# AVRI2CIO.net
KiCad netlist of a schematic drawn in EAGLE
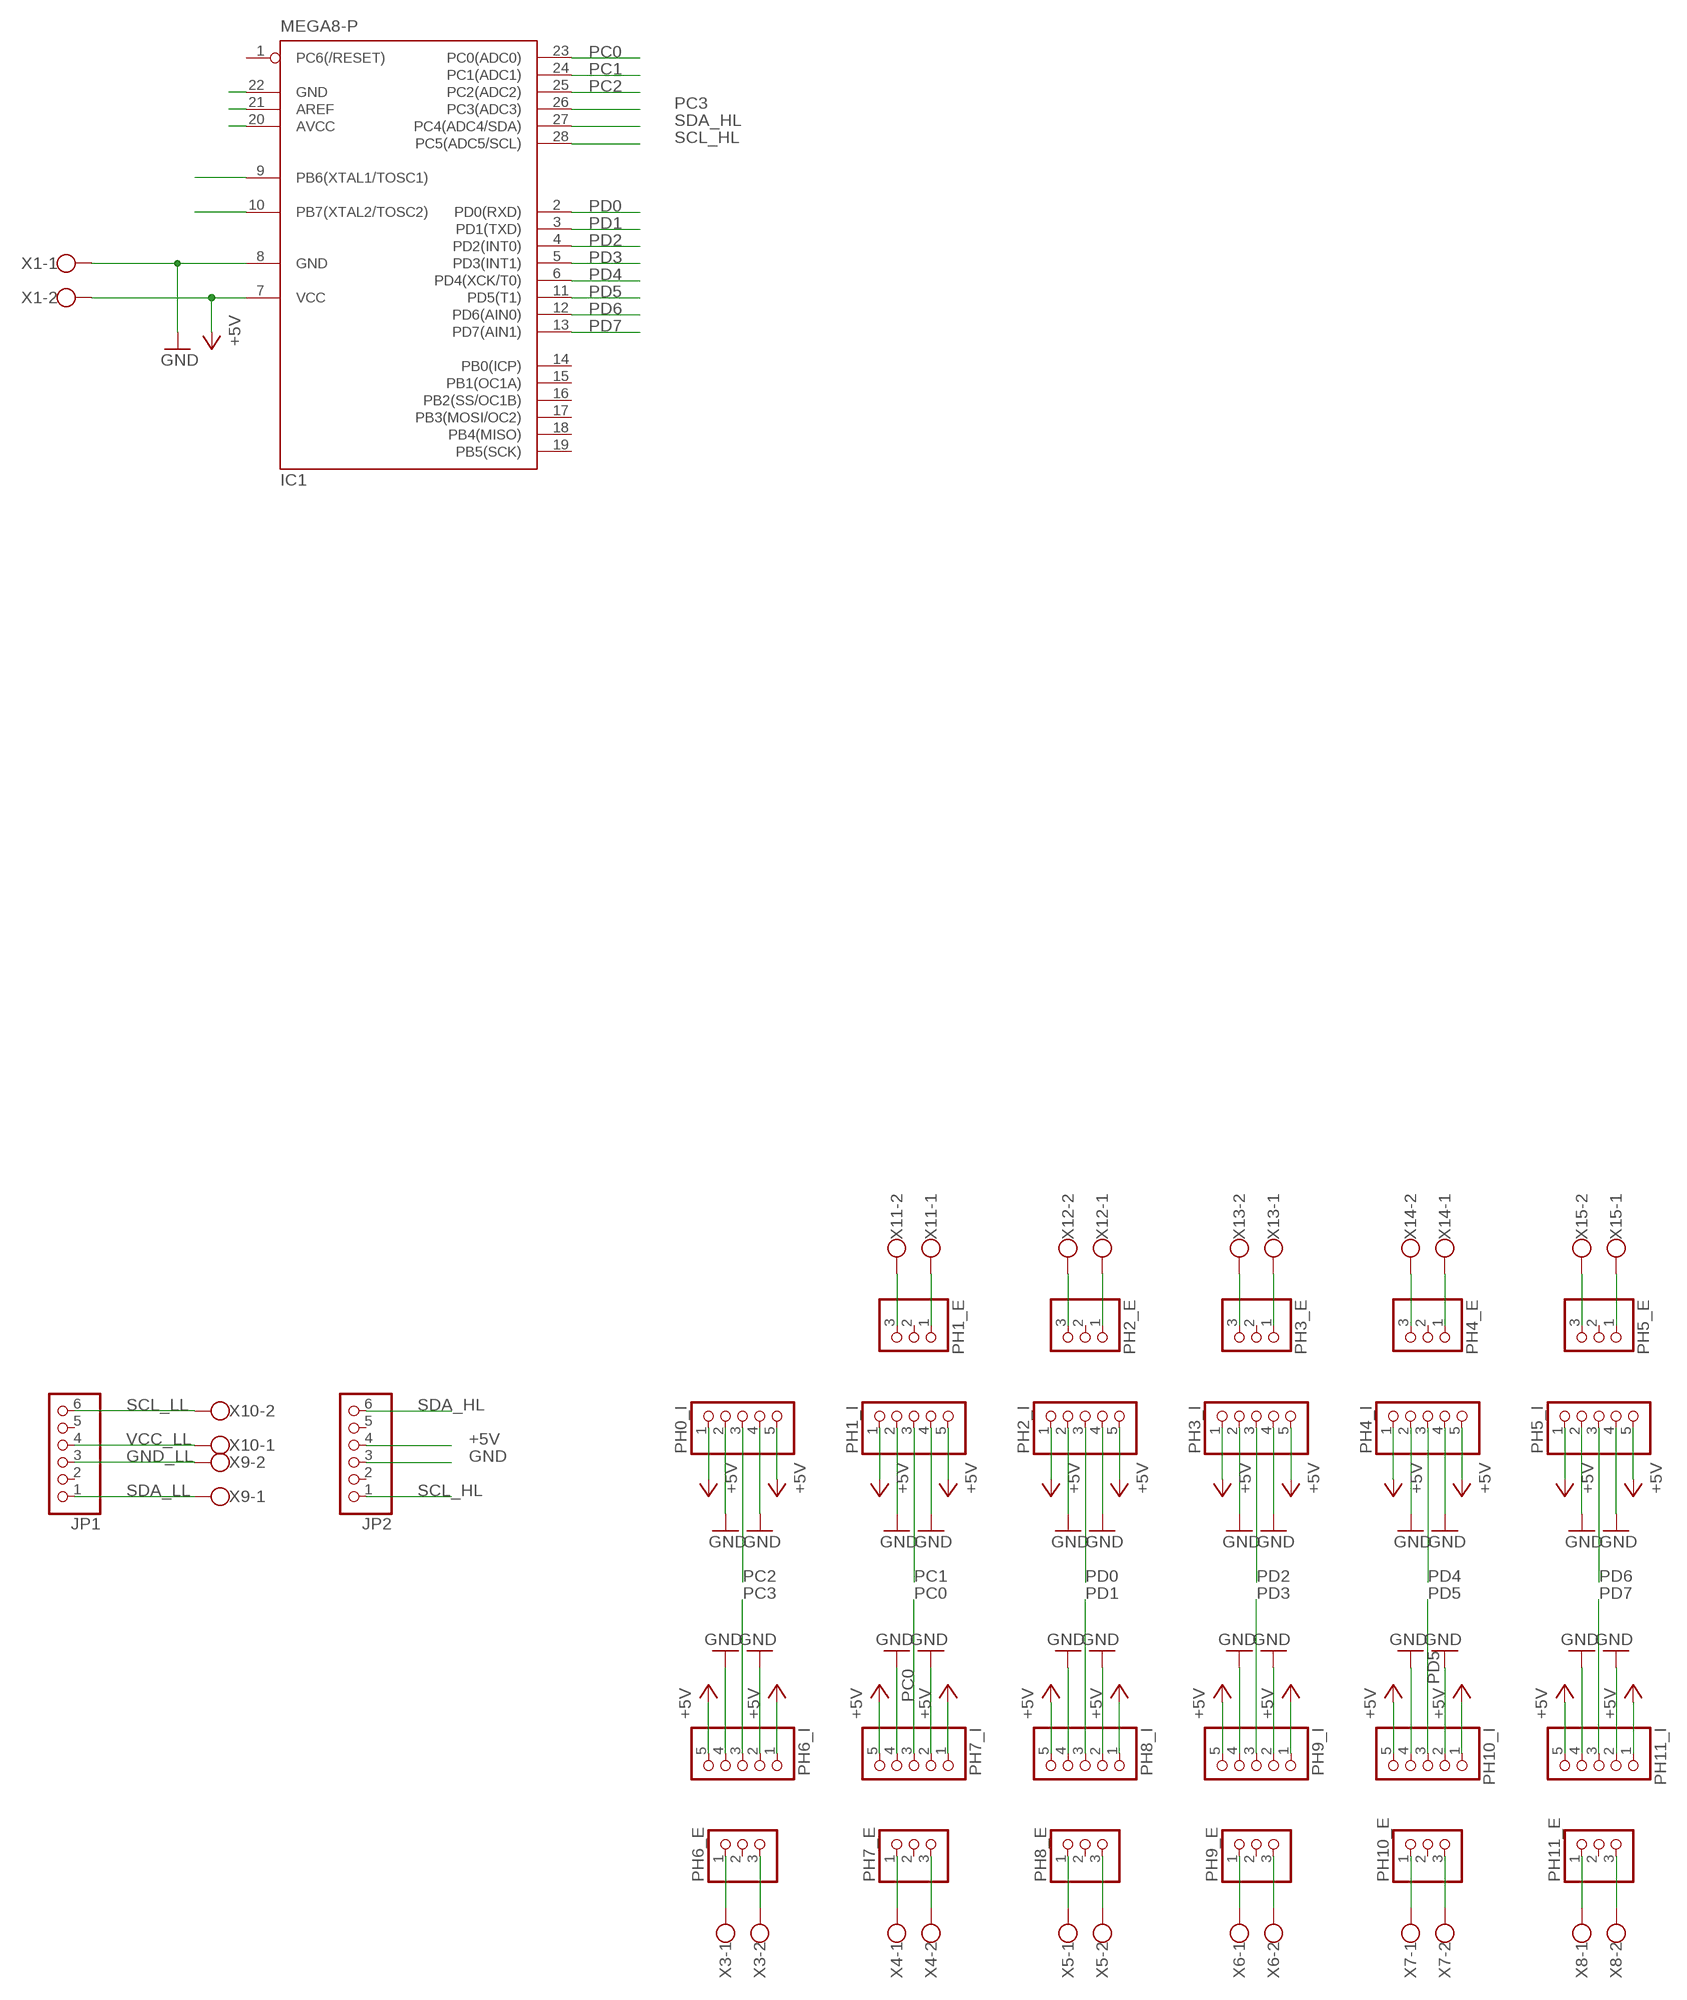
[diagram p0: schematic, sheet 1]

(export (version "E")
  (design (tool "Eeschema 10.0.6"))
  (components
    (comp (ref "IC1")
      (value "MEGA8-P")
      (footprint "eagle-import:DIL28-3")
      (libsource (lib "eagle-import") (part "MEGA8-P"))
    )
    (comp (ref "JP1")
      (value "PINHD-1X6")
      (footprint "eagle-import:1X06")
      (libsource (lib "eagle-import") (part "PINHD-1X6"))
    )
    (comp (ref "JP2")
      (value "PINHD-1X6")
      (footprint "eagle-import:1X06")
      (libsource (lib "eagle-import") (part "PINHD-1X6"))
    )
    (comp (ref "PH0_I")
      (value "PINHD-1X5")
      (footprint "eagle-import:1X05")
      (libsource (lib "eagle-import") (part "PINHD-1X5"))
    )
    (comp (ref "PH1_E")
      (value "PINHD-1X3")
      (footprint "eagle-import:1X03")
      (libsource (lib "eagle-import") (part "PINHD-1X3"))
    )
    (comp (ref "PH1_I")
      (value "PINHD-1X5")
      (footprint "eagle-import:1X05")
      (libsource (lib "eagle-import") (part "PINHD-1X5"))
    )
    (comp (ref "PH2_E")
      (value "PINHD-1X3")
      (footprint "eagle-import:1X03")
      (libsource (lib "eagle-import") (part "PINHD-1X3"))
    )
    (comp (ref "PH2_I")
      (value "PINHD-1X5")
      (footprint "eagle-import:1X05")
      (libsource (lib "eagle-import") (part "PINHD-1X5"))
    )
    (comp (ref "PH3_E")
      (value "PINHD-1X3")
      (footprint "eagle-import:1X03")
      (libsource (lib "eagle-import") (part "PINHD-1X3"))
    )
    (comp (ref "PH3_I")
      (value "PINHD-1X5")
      (footprint "eagle-import:1X05")
      (libsource (lib "eagle-import") (part "PINHD-1X5"))
    )
    (comp (ref "PH4_E")
      (value "PINHD-1X3")
      (footprint "eagle-import:1X03")
      (libsource (lib "eagle-import") (part "PINHD-1X3"))
    )
    (comp (ref "PH4_I")
      (value "PINHD-1X5")
      (footprint "eagle-import:1X05")
      (libsource (lib "eagle-import") (part "PINHD-1X5"))
    )
    (comp (ref "PH5_E")
      (value "PINHD-1X3")
      (footprint "eagle-import:1X03")
      (libsource (lib "eagle-import") (part "PINHD-1X3"))
    )
    (comp (ref "PH5_I")
      (value "PINHD-1X5")
      (footprint "eagle-import:1X05")
      (libsource (lib "eagle-import") (part "PINHD-1X5"))
    )
    (comp (ref "PH6_E")
      (value "PINHD-1X3")
      (footprint "eagle-import:1X03")
      (libsource (lib "eagle-import") (part "PINHD-1X3"))
    )
    (comp (ref "PH6_I")
      (value "PINHD-1X5")
      (footprint "eagle-import:1X05")
      (libsource (lib "eagle-import") (part "PINHD-1X5"))
    )
    (comp (ref "PH7_E")
      (value "PINHD-1X3")
      (footprint "eagle-import:1X03")
      (libsource (lib "eagle-import") (part "PINHD-1X3"))
    )
    (comp (ref "PH7_I")
      (value "PINHD-1X5")
      (footprint "eagle-import:1X05")
      (libsource (lib "eagle-import") (part "PINHD-1X5"))
    )
    (comp (ref "PH8_E")
      (value "PINHD-1X3")
      (footprint "eagle-import:1X03")
      (libsource (lib "eagle-import") (part "PINHD-1X3"))
    )
    (comp (ref "PH8_I")
      (value "PINHD-1X5")
      (footprint "eagle-import:1X05")
      (libsource (lib "eagle-import") (part "PINHD-1X5"))
    )
    (comp (ref "PH9_E")
      (value "PINHD-1X3")
      (footprint "eagle-import:1X03")
      (libsource (lib "eagle-import") (part "PINHD-1X3"))
    )
    (comp (ref "PH9_I")
      (value "PINHD-1X5")
      (footprint "eagle-import:1X05")
      (libsource (lib "eagle-import") (part "PINHD-1X5"))
    )
    (comp (ref "PH10_E")
      (value "PINHD-1X3")
      (footprint "eagle-import:1X03")
      (libsource (lib "eagle-import") (part "PINHD-1X3"))
    )
    (comp (ref "PH10_I")
      (value "PINHD-1X5")
      (footprint "eagle-import:1X05")
      (libsource (lib "eagle-import") (part "PINHD-1X5"))
    )
    (comp (ref "PH11_E")
      (value "PINHD-1X3")
      (footprint "eagle-import:1X03")
      (libsource (lib "eagle-import") (part "PINHD-1X3"))
    )
    (comp (ref "PH11_I")
      (value "PINHD-1X5")
      (footprint "eagle-import:1X05")
      (libsource (lib "eagle-import") (part "PINHD-1X5"))
    )
    (comp (ref "X1")
      (value "W237-102")
      (footprint "eagle-import:W237-102")
      (fields (field (name "MPN") "237-102"))
      (libsource (lib "eagle-import") (part "W237-102"))
    )
    (comp (ref "X3")
      (value "W237-102")
      (footprint "eagle-import:W237-102")
      (fields (field (name "MPN") "237-102"))
      (libsource (lib "eagle-import") (part "W237-102"))
    )
    (comp (ref "X4")
      (value "W237-102")
      (footprint "eagle-import:W237-102")
      (fields (field (name "MPN") "237-102"))
      (libsource (lib "eagle-import") (part "W237-102"))
    )
    (comp (ref "X5")
      (value "W237-102")
      (footprint "eagle-import:W237-102")
      (fields (field (name "MPN") "237-102"))
      (libsource (lib "eagle-import") (part "W237-102"))
    )
    (comp (ref "X6")
      (value "W237-102")
      (footprint "eagle-import:W237-102")
      (fields (field (name "MPN") "237-102"))
      (libsource (lib "eagle-import") (part "W237-102"))
    )
    (comp (ref "X7")
      (value "W237-102")
      (footprint "eagle-import:W237-102")
      (fields (field (name "MPN") "237-102"))
      (libsource (lib "eagle-import") (part "W237-102"))
    )
    (comp (ref "X8")
      (value "W237-102")
      (footprint "eagle-import:W237-102")
      (fields (field (name "MPN") "237-102"))
      (libsource (lib "eagle-import") (part "W237-102"))
    )
    (comp (ref "X9")
      (value "W237-102")
      (footprint "eagle-import:W237-102")
      (fields (field (name "MPN") "237-102"))
      (libsource (lib "eagle-import") (part "W237-102"))
    )
    (comp (ref "X10")
      (value "W237-102")
      (footprint "eagle-import:W237-102")
      (fields (field (name "MPN") "237-102"))
      (libsource (lib "eagle-import") (part "W237-102"))
    )
    (comp (ref "X11")
      (value "W237-102")
      (footprint "eagle-import:W237-102")
      (fields (field (name "MPN") "237-102"))
      (libsource (lib "eagle-import") (part "W237-102"))
    )
    (comp (ref "X12")
      (value "W237-102")
      (footprint "eagle-import:W237-102")
      (fields (field (name "MPN") "237-102"))
      (libsource (lib "eagle-import") (part "W237-102"))
    )
    (comp (ref "X13")
      (value "W237-102")
      (footprint "eagle-import:W237-102")
      (fields (field (name "MPN") "237-102"))
      (libsource (lib "eagle-import") (part "W237-102"))
    )
    (comp (ref "X14")
      (value "W237-102")
      (footprint "eagle-import:W237-102")
      (fields (field (name "MPN") "237-102"))
      (libsource (lib "eagle-import") (part "W237-102"))
    )
    (comp (ref "X15")
      (value "W237-102")
      (footprint "eagle-import:W237-102")
      (fields (field (name "MPN") "237-102"))
      (libsource (lib "eagle-import") (part "W237-102"))
    )
  )
  (nets
    (net (code "1") (name "+5V") (class "Default")
      (node (ref "IC1") (pin "7") (pinfunction "VCC_7") (pintype "power_in"))
      (node (ref "JP2") (pin "4") (pinfunction "4_4") (pintype "passive"))
      (node (ref "PH0_I") (pin "1") (pinfunction "1_1") (pintype "passive"))
      (node (ref "PH0_I") (pin "5") (pinfunction "5_5") (pintype "passive"))
      (node (ref "PH10_I") (pin "1") (pinfunction "1_1") (pintype "passive"))
      (node (ref "PH10_I") (pin "5") (pinfunction "5_5") (pintype "passive"))
      (node (ref "PH11_I") (pin "1") (pinfunction "1_1") (pintype "passive"))
      (node (ref "PH11_I") (pin "5") (pinfunction "5_5") (pintype "passive"))
      (node (ref "PH1_I") (pin "1") (pinfunction "1_1") (pintype "passive"))
      (node (ref "PH1_I") (pin "5") (pinfunction "5_5") (pintype "passive"))
      (node (ref "PH2_I") (pin "1") (pinfunction "1_1") (pintype "passive"))
      (node (ref "PH2_I") (pin "5") (pinfunction "5_5") (pintype "passive"))
      (node (ref "PH3_I") (pin "1") (pinfunction "1_1") (pintype "passive"))
      (node (ref "PH3_I") (pin "5") (pinfunction "5_5") (pintype "passive"))
      (node (ref "PH4_I") (pin "1") (pinfunction "1_1") (pintype "passive"))
      (node (ref "PH4_I") (pin "5") (pinfunction "5_5") (pintype "passive"))
      (node (ref "PH5_I") (pin "1") (pinfunction "1_1") (pintype "passive"))
      (node (ref "PH5_I") (pin "5") (pinfunction "5_5") (pintype "passive"))
      (node (ref "PH6_I") (pin "1") (pinfunction "1_1") (pintype "passive"))
      (node (ref "PH6_I") (pin "5") (pinfunction "5_5") (pintype "passive"))
      (node (ref "PH7_I") (pin "1") (pinfunction "1_1") (pintype "passive"))
      (node (ref "PH7_I") (pin "5") (pinfunction "5_5") (pintype "passive"))
      (node (ref "PH8_I") (pin "1") (pinfunction "1_1") (pintype "passive"))
      (node (ref "PH8_I") (pin "5") (pinfunction "5_5") (pintype "passive"))
      (node (ref "PH9_I") (pin "1") (pinfunction "1_1") (pintype "passive"))
      (node (ref "PH9_I") (pin "5") (pinfunction "5_5") (pintype "passive"))
      (node (ref "X1") (pin "2") (pinfunction "KL_2") (pintype "passive"))
    )
    (net (code "2") (name "/GND_LL") (class "Default")
      (node (ref "JP1") (pin "3") (pinfunction "3_3") (pintype "passive"))
      (node (ref "X9") (pin "2") (pinfunction "KL_2") (pintype "passive"))
    )
    (net (code "3") (name "/PC0") (class "Default")
      (node (ref "IC1") (pin "23") (pinfunction "PC0(ADC0)_23") (pintype "bidirectional"))
      (node (ref "PH7_I") (pin "3") (pinfunction "3_3") (pintype "passive"))
    )
    (net (code "4") (name "/PC1") (class "Default")
      (node (ref "IC1") (pin "24") (pinfunction "PC1(ADC1)_24") (pintype "bidirectional"))
      (node (ref "PH1_I") (pin "3") (pinfunction "3_3") (pintype "passive"))
    )
    (net (code "5") (name "/PC2") (class "Default")
      (node (ref "IC1") (pin "25") (pinfunction "PC2(ADC2)_25") (pintype "bidirectional"))
      (node (ref "PH0_I") (pin "3") (pinfunction "3_3") (pintype "passive"))
    )
    (net (code "6") (name "/PC3") (class "Default")
      (node (ref "IC1") (pin "26") (pinfunction "PC3(ADC3)_26") (pintype "bidirectional"))
      (node (ref "PH6_I") (pin "3") (pinfunction "3_3") (pintype "passive"))
    )
    (net (code "7") (name "/PD0") (class "Default")
      (node (ref "IC1") (pin "2") (pinfunction "PD0(RXD)_2") (pintype "bidirectional"))
      (node (ref "PH2_I") (pin "3") (pinfunction "3_3") (pintype "passive"))
    )
    (net (code "8") (name "/PD1") (class "Default")
      (node (ref "IC1") (pin "3") (pinfunction "PD1(TXD)_3") (pintype "bidirectional"))
      (node (ref "PH8_I") (pin "3") (pinfunction "3_3") (pintype "passive"))
    )
    (net (code "9") (name "/PD2") (class "Default")
      (node (ref "IC1") (pin "4") (pinfunction "PD2(INT0)_4") (pintype "bidirectional"))
      (node (ref "PH3_I") (pin "3") (pinfunction "3_3") (pintype "passive"))
    )
    (net (code "10") (name "/PD3") (class "Default")
      (node (ref "IC1") (pin "5") (pinfunction "PD3(INT1)_5") (pintype "bidirectional"))
      (node (ref "PH9_I") (pin "3") (pinfunction "3_3") (pintype "passive"))
    )
    (net (code "11") (name "/PD4") (class "Default")
      (node (ref "IC1") (pin "6") (pinfunction "PD4(XCK/T0)_6") (pintype "bidirectional"))
      (node (ref "PH4_I") (pin "3") (pinfunction "3_3") (pintype "passive"))
    )
    (net (code "12") (name "/PD5") (class "Default")
      (node (ref "IC1") (pin "11") (pinfunction "PD5(T1)_11") (pintype "bidirectional"))
      (node (ref "PH10_I") (pin "3") (pinfunction "3_3") (pintype "passive"))
    )
    (net (code "13") (name "/PD6") (class "Default")
      (node (ref "IC1") (pin "12") (pinfunction "PD6(AIN0)_12") (pintype "bidirectional"))
      (node (ref "PH5_I") (pin "3") (pinfunction "3_3") (pintype "passive"))
    )
    (net (code "14") (name "/PD7") (class "Default")
      (node (ref "IC1") (pin "13") (pinfunction "PD7(AIN1)_13") (pintype "bidirectional"))
      (node (ref "PH11_I") (pin "3") (pinfunction "3_3") (pintype "passive"))
    )
    (net (code "15") (name "/SCL_HL") (class "Default")
      (node (ref "IC1") (pin "28") (pinfunction "PC5(ADC5/SCL)_28") (pintype "bidirectional"))
      (node (ref "JP2") (pin "1") (pinfunction "1_1") (pintype "passive"))
    )
    (net (code "16") (name "/SCL_LL") (class "Default")
      (node (ref "JP1") (pin "6") (pinfunction "6_6") (pintype "passive"))
      (node (ref "X10") (pin "2") (pinfunction "KL_2") (pintype "passive"))
    )
    (net (code "17") (name "/SDA_HL") (class "Default")
      (node (ref "IC1") (pin "27") (pinfunction "PC4(ADC4/SDA)_27") (pintype "bidirectional"))
      (node (ref "JP2") (pin "6") (pinfunction "6_6") (pintype "passive"))
    )
    (net (code "18") (name "/SDA_LL") (class "Default")
      (node (ref "JP1") (pin "1") (pinfunction "1_1") (pintype "passive"))
      (node (ref "X9") (pin "1") (pinfunction "KL_1") (pintype "passive"))
    )
    (net (code "19") (name "/VCC_LL") (class "Default")
      (node (ref "JP1") (pin "4") (pinfunction "4_4") (pintype "passive"))
      (node (ref "X10") (pin "1") (pinfunction "KL_1") (pintype "passive"))
    )
    (net (code "20") (name "GND") (class "Default")
      (node (ref "IC1") (pin "8") (pinfunction "GND_8") (pintype "power_in"))
      (node (ref "JP2") (pin "3") (pinfunction "3_3") (pintype "passive"))
      (node (ref "PH0_I") (pin "2") (pinfunction "2_2") (pintype "passive"))
      (node (ref "PH0_I") (pin "4") (pinfunction "4_4") (pintype "passive"))
      (node (ref "PH10_I") (pin "2") (pinfunction "2_2") (pintype "passive"))
      (node (ref "PH10_I") (pin "4") (pinfunction "4_4") (pintype "passive"))
      (node (ref "PH11_I") (pin "2") (pinfunction "2_2") (pintype "passive"))
      (node (ref "PH11_I") (pin "4") (pinfunction "4_4") (pintype "passive"))
      (node (ref "PH1_I") (pin "2") (pinfunction "2_2") (pintype "passive"))
      (node (ref "PH1_I") (pin "4") (pinfunction "4_4") (pintype "passive"))
      (node (ref "PH2_I") (pin "2") (pinfunction "2_2") (pintype "passive"))
      (node (ref "PH2_I") (pin "4") (pinfunction "4_4") (pintype "passive"))
      (node (ref "PH3_I") (pin "2") (pinfunction "2_2") (pintype "passive"))
      (node (ref "PH3_I") (pin "4") (pinfunction "4_4") (pintype "passive"))
      (node (ref "PH4_I") (pin "2") (pinfunction "2_2") (pintype "passive"))
      (node (ref "PH4_I") (pin "4") (pinfunction "4_4") (pintype "passive"))
      (node (ref "PH5_I") (pin "2") (pinfunction "2_2") (pintype "passive"))
      (node (ref "PH5_I") (pin "4") (pinfunction "4_4") (pintype "passive"))
      (node (ref "PH6_I") (pin "2") (pinfunction "2_2") (pintype "passive"))
      (node (ref "PH6_I") (pin "4") (pinfunction "4_4") (pintype "passive"))
      (node (ref "PH7_I") (pin "2") (pinfunction "2_2") (pintype "passive"))
      (node (ref "PH7_I") (pin "4") (pinfunction "4_4") (pintype "passive"))
      (node (ref "PH8_I") (pin "2") (pinfunction "2_2") (pintype "passive"))
      (node (ref "PH8_I") (pin "4") (pinfunction "4_4") (pintype "passive"))
      (node (ref "PH9_I") (pin "2") (pinfunction "2_2") (pintype "passive"))
      (node (ref "PH9_I") (pin "4") (pinfunction "4_4") (pintype "passive"))
      (node (ref "X1") (pin "1") (pinfunction "KL_1") (pintype "passive"))
    )
    (net (code "21") (name "Net-(X3A-KL)") (class "Default")
      (node (ref "PH6_E") (pin "1") (pinfunction "1_1") (pintype "passive"))
      (node (ref "X3") (pin "1") (pinfunction "KL_1") (pintype "passive"))
    )
    (net (code "22") (name "Net-(X3B-KL)") (class "Default")
      (node (ref "PH6_E") (pin "3") (pinfunction "3_3") (pintype "passive"))
      (node (ref "X3") (pin "2") (pinfunction "KL_2") (pintype "passive"))
    )
    (net (code "23") (name "Net-(X4A-KL)") (class "Default")
      (node (ref "PH7_E") (pin "1") (pinfunction "1_1") (pintype "passive"))
      (node (ref "X4") (pin "1") (pinfunction "KL_1") (pintype "passive"))
    )
    (net (code "24") (name "Net-(X4B-KL)") (class "Default")
      (node (ref "PH7_E") (pin "3") (pinfunction "3_3") (pintype "passive"))
      (node (ref "X4") (pin "2") (pinfunction "KL_2") (pintype "passive"))
    )
    (net (code "25") (name "Net-(X5A-KL)") (class "Default")
      (node (ref "PH8_E") (pin "1") (pinfunction "1_1") (pintype "passive"))
      (node (ref "X5") (pin "1") (pinfunction "KL_1") (pintype "passive"))
    )
    (net (code "26") (name "Net-(X5B-KL)") (class "Default")
      (node (ref "PH8_E") (pin "3") (pinfunction "3_3") (pintype "passive"))
      (node (ref "X5") (pin "2") (pinfunction "KL_2") (pintype "passive"))
    )
    (net (code "27") (name "Net-(X6A-KL)") (class "Default")
      (node (ref "PH9_E") (pin "1") (pinfunction "1_1") (pintype "passive"))
      (node (ref "X6") (pin "1") (pinfunction "KL_1") (pintype "passive"))
    )
    (net (code "28") (name "Net-(X6B-KL)") (class "Default")
      (node (ref "PH9_E") (pin "3") (pinfunction "3_3") (pintype "passive"))
      (node (ref "X6") (pin "2") (pinfunction "KL_2") (pintype "passive"))
    )
    (net (code "29") (name "Net-(X7A-KL)") (class "Default")
      (node (ref "PH10_E") (pin "1") (pinfunction "1_1") (pintype "passive"))
      (node (ref "X7") (pin "1") (pinfunction "KL_1") (pintype "passive"))
    )
    (net (code "30") (name "Net-(X7B-KL)") (class "Default")
      (node (ref "PH10_E") (pin "3") (pinfunction "3_3") (pintype "passive"))
      (node (ref "X7") (pin "2") (pinfunction "KL_2") (pintype "passive"))
    )
    (net (code "31") (name "Net-(X8A-KL)") (class "Default")
      (node (ref "PH11_E") (pin "1") (pinfunction "1_1") (pintype "passive"))
      (node (ref "X8") (pin "1") (pinfunction "KL_1") (pintype "passive"))
    )
    (net (code "32") (name "Net-(X8B-KL)") (class "Default")
      (node (ref "PH11_E") (pin "3") (pinfunction "3_3") (pintype "passive"))
      (node (ref "X8") (pin "2") (pinfunction "KL_2") (pintype "passive"))
    )
    (net (code "33") (name "Net-(X11A-KL)") (class "Default")
      (node (ref "PH1_E") (pin "1") (pinfunction "1_1") (pintype "passive"))
      (node (ref "X11") (pin "1") (pinfunction "KL_1") (pintype "passive"))
    )
    (net (code "34") (name "Net-(X11B-KL)") (class "Default")
      (node (ref "PH1_E") (pin "3") (pinfunction "3_3") (pintype "passive"))
      (node (ref "X11") (pin "2") (pinfunction "KL_2") (pintype "passive"))
    )
    (net (code "35") (name "Net-(X12A-KL)") (class "Default")
      (node (ref "PH2_E") (pin "1") (pinfunction "1_1") (pintype "passive"))
      (node (ref "X12") (pin "1") (pinfunction "KL_1") (pintype "passive"))
    )
    (net (code "36") (name "Net-(X12B-KL)") (class "Default")
      (node (ref "PH2_E") (pin "3") (pinfunction "3_3") (pintype "passive"))
      (node (ref "X12") (pin "2") (pinfunction "KL_2") (pintype "passive"))
    )
    (net (code "37") (name "Net-(X13A-KL)") (class "Default")
      (node (ref "PH3_E") (pin "1") (pinfunction "1_1") (pintype "passive"))
      (node (ref "X13") (pin "1") (pinfunction "KL_1") (pintype "passive"))
    )
    (net (code "38") (name "Net-(X13B-KL)") (class "Default")
      (node (ref "PH3_E") (pin "3") (pinfunction "3_3") (pintype "passive"))
      (node (ref "X13") (pin "2") (pinfunction "KL_2") (pintype "passive"))
    )
    (net (code "39") (name "Net-(X14A-KL)") (class "Default")
      (node (ref "PH4_E") (pin "1") (pinfunction "1_1") (pintype "passive"))
      (node (ref "X14") (pin "1") (pinfunction "KL_1") (pintype "passive"))
    )
    (net (code "40") (name "Net-(X14B-KL)") (class "Default")
      (node (ref "PH4_E") (pin "3") (pinfunction "3_3") (pintype "passive"))
      (node (ref "X14") (pin "2") (pinfunction "KL_2") (pintype "passive"))
    )
    (net (code "41") (name "Net-(X15A-KL)") (class "Default")
      (node (ref "PH5_E") (pin "1") (pinfunction "1_1") (pintype "passive"))
      (node (ref "X15") (pin "1") (pinfunction "KL_1") (pintype "passive"))
    )
    (net (code "42") (name "Net-(X15B-KL)") (class "Default")
      (node (ref "PH5_E") (pin "3") (pinfunction "3_3") (pintype "passive"))
      (node (ref "X15") (pin "2") (pinfunction "KL_2") (pintype "passive"))
    )
    (net (code "43") (name "unconnected-(IC1-AREF-Pad21)") (class "Default")
      (node (ref "IC1") (pin "21") (pinfunction "AREF_21") (pintype "passive"))
    )
    (net (code "44") (name "unconnected-(IC1-AVCC-Pad20)") (class "Default")
      (node (ref "IC1") (pin "20") (pinfunction "AVCC_20") (pintype "power_in"))
    )
    (net (code "45") (name "unconnected-(IC1-GND-Pad22)") (class "Default")
      (node (ref "IC1") (pin "22") (pinfunction "GND_22") (pintype "power_in"))
    )
    (net (code "46") (name "unconnected-(IC1-PB0(ICP)-Pad14)") (class "Default")
      (node (ref "IC1") (pin "14") (pinfunction "PB0(ICP)_14") (pintype "bidirectional"))
    )
    (net (code "47") (name "unconnected-(IC1-PB1(OC1A)-Pad15)") (class "Default")
      (node (ref "IC1") (pin "15") (pinfunction "PB1(OC1A)_15") (pintype "bidirectional"))
    )
    (net (code "48") (name "unconnected-(IC1-PB2(SS{slash}OC1B)-Pad16)") (class "Default")
      (node (ref "IC1") (pin "16") (pinfunction "PB2(SS/OC1B)_16") (pintype "bidirectional"))
    )
    (net (code "49") (name "unconnected-(IC1-PB3(MOSI{slash}OC2)-Pad17)") (class "Default")
      (node (ref "IC1") (pin "17") (pinfunction "PB3(MOSI/OC2)_17") (pintype "bidirectional"))
    )
    (net (code "50") (name "unconnected-(IC1-PB4(MISO)-Pad18)") (class "Default")
      (node (ref "IC1") (pin "18") (pinfunction "PB4(MISO)_18") (pintype "bidirectional"))
    )
    (net (code "51") (name "unconnected-(IC1-PB5(SCK)-Pad19)") (class "Default")
      (node (ref "IC1") (pin "19") (pinfunction "PB5(SCK)_19") (pintype "bidirectional"))
    )
    (net (code "52") (name "unconnected-(IC1-PB6(XTAL1{slash}TOSC1)-Pad9)") (class "Default")
      (node (ref "IC1") (pin "9") (pinfunction "PB6(XTAL1/TOSC1)_9") (pintype "bidirectional"))
    )
    (net (code "53") (name "unconnected-(IC1-PB7(XTAL2{slash}TOSC2)-Pad10)") (class "Default")
      (node (ref "IC1") (pin "10") (pinfunction "PB7(XTAL2/TOSC2)_10") (pintype "bidirectional"))
    )
    (net (code "54") (name "unconnected-(IC1-PC6({slash}RESET)-Pad1)") (class "Default")
      (node (ref "IC1") (pin "1") (pinfunction "PC6(/RESET)_1") (pintype "bidirectional"))
    )
    (net (code "55") (name "unconnected-(JP1-Pad2)") (class "Default")
      (node (ref "JP1") (pin "2") (pinfunction "2_2") (pintype "passive"))
    )
    (net (code "56") (name "unconnected-(JP1-Pad5)") (class "Default")
      (node (ref "JP1") (pin "5") (pinfunction "5_5") (pintype "passive"))
    )
    (net (code "57") (name "unconnected-(JP2-Pad2)") (class "Default")
      (node (ref "JP2") (pin "2") (pinfunction "2_2") (pintype "passive"))
    )
    (net (code "58") (name "unconnected-(JP2-Pad5)") (class "Default")
      (node (ref "JP2") (pin "5") (pinfunction "5_5") (pintype "passive"))
    )
    (net (code "59") (name "unconnected-(PH1_E-Pad2)") (class "Default")
      (node (ref "PH1_E") (pin "2") (pinfunction "2_2") (pintype "passive"))
    )
    (net (code "60") (name "unconnected-(PH2_E-Pad2)") (class "Default")
      (node (ref "PH2_E") (pin "2") (pinfunction "2_2") (pintype "passive"))
    )
    (net (code "61") (name "unconnected-(PH3_E-Pad2)") (class "Default")
      (node (ref "PH3_E") (pin "2") (pinfunction "2_2") (pintype "passive"))
    )
    (net (code "62") (name "unconnected-(PH4_E-Pad2)") (class "Default")
      (node (ref "PH4_E") (pin "2") (pinfunction "2_2") (pintype "passive"))
    )
    (net (code "63") (name "unconnected-(PH5_E-Pad2)") (class "Default")
      (node (ref "PH5_E") (pin "2") (pinfunction "2_2") (pintype "passive"))
    )
    (net (code "64") (name "unconnected-(PH6_E-Pad2)") (class "Default")
      (node (ref "PH6_E") (pin "2") (pinfunction "2_2") (pintype "passive"))
    )
    (net (code "65") (name "unconnected-(PH7_E-Pad2)") (class "Default")
      (node (ref "PH7_E") (pin "2") (pinfunction "2_2") (pintype "passive"))
    )
    (net (code "66") (name "unconnected-(PH8_E-Pad2)") (class "Default")
      (node (ref "PH8_E") (pin "2") (pinfunction "2_2") (pintype "passive"))
    )
    (net (code "67") (name "unconnected-(PH9_E-Pad2)") (class "Default")
      (node (ref "PH9_E") (pin "2") (pinfunction "2_2") (pintype "passive"))
    )
    (net (code "68") (name "unconnected-(PH10_E-Pad2)") (class "Default")
      (node (ref "PH10_E") (pin "2") (pinfunction "2_2") (pintype "passive"))
    )
    (net (code "69") (name "unconnected-(PH11_E-Pad2)") (class "Default")
      (node (ref "PH11_E") (pin "2") (pinfunction "2_2") (pintype "passive"))
    )
  )
)
